# PCB_Steering_Wheel_REDO.net
KiCad netlist of a schematic drawn in Altium Designer
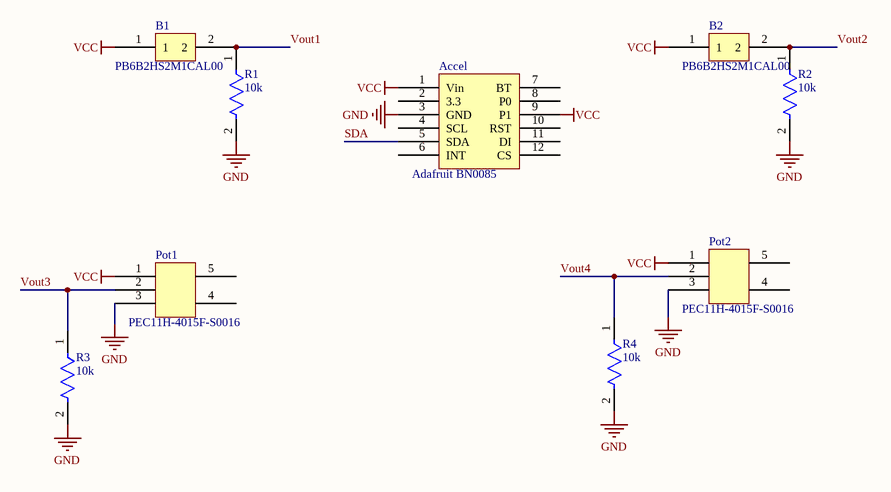
[diagram p0: PCB_Steering_Wheel_REDO.SchDoc]

(export (version "E")
  (design (tool "Eeschema 10.0.6"))
  (components
    (comp (ref "Accel")
      (value "Adafruit BN0085")
      (footprint "Adafruit BN0085-Footprint-1")
      (description "9DoF Accel/Gyro")
      (libsource (lib "Bradford Bawden") (part "New symbol 1"))
    )
    (comp (ref "B1")
      (value "PB6B2HS2M1CAL00")
      (footprint "PB6B2HS2M1CAL00-Footprint-1")
      (description "Standard PB6 Black Panel Mount Front Pushbutton Switch 125mA AC 200mA DC 125V -30C~85C")
      (libsource (lib "Bradford Bawden") (part "PB6B2HS2M1CAL00-Symbol-1"))
    )
    (comp (ref "B2")
      (value "PB6B2HS2M1CAL00")
      (footprint "PB6B2HS2M1CAL00-Footprint-1")
      (description "Standard PB6 Black Panel Mount Front Pushbutton Switch 125mA AC 200mA DC 125V -30C~85C")
      (libsource (lib "Bradford Bawden") (part "PB6B2HS2M1CAL00-Symbol-1"))
    )
    (comp (ref "Pot1")
      (value "PEC11H-4015F-S0016")
      (footprint "PEC11H-4015F-S0016-Footprint-1")
      (description "INCREMENTAL ENCODER, 2CH, 60 RPM, 16 PPR; Encoder Technology: Mechanical; Type: Incremental;")
      (libsource (lib "Bradford Bawden") (part "PEC11H-4015F-S0016-Symbol-1"))
    )
    (comp (ref "Pot2")
      (value "PEC11H-4015F-S0016")
      (footprint "PEC11H-4015F-S0016-Footprint-1")
      (description "INCREMENTAL ENCODER, 2CH, 60 RPM, 16 PPR; Encoder Technology: Mechanical; Type: Incremental;")
      (libsource (lib "Bradford Bawden") (part "PEC11H-4015F-S0016-Symbol-1"))
    )
    (comp (ref "R1")
      (value "10k")
      (footprint "FP-H45K0BAA-MFG")
      (description "RES 5.00K OHM 1/2W 0.1% AXIAL")
      (fields (field (name "TOLERANCE") "0.1%"))
      (libsource (lib "Altium Content Vault") (part "1029c3af85768c4190bb7ad29bc67b5"))
    )
    (comp (ref "R2")
      (value "10k")
      (footprint "FP-H45K0BAA-MFG")
      (description "RES 5.00K OHM 1/2W 0.1% AXIAL")
      (fields (field (name "TOLERANCE") "0.1%"))
      (libsource (lib "Altium Content Vault") (part "1029c3af85768c4190bb7ad29bc67b5"))
    )
    (comp (ref "R3")
      (value "10k")
      (footprint "FP-H45K0BAA-MFG")
      (description "RES 5.00K OHM 1/2W 0.1% AXIAL")
      (fields (field (name "TOLERANCE") "0.1%"))
      (libsource (lib "Altium Content Vault") (part "1029c3af85768c4190bb7ad29bc67b5"))
    )
    (comp (ref "R4")
      (value "10k")
      (footprint "FP-H45K0BAA-MFG")
      (description "RES 5.00K OHM 1/2W 0.1% AXIAL")
      (fields (field (name "TOLERANCE") "0.1%"))
      (libsource (lib "Altium Content Vault") (part "1029c3af85768c4190bb7ad29bc67b5"))
    )
  )
  (nets
    (net (code "1") (name "/SDA") (class "Default")
      (node (ref "Accel") (pin "5") (pinfunction "SDA_5") (pintype "passive"))
    )
    (net (code "2") (name "/Vout1") (class "Default")
      (node (ref "B1") (pin "2") (pinfunction "2_2") (pintype "passive"))
      (node (ref "R1") (pin "1") (pinfunction "1_1") (pintype "passive"))
    )
    (net (code "3") (name "/Vout2") (class "Default")
      (node (ref "B2") (pin "2") (pinfunction "2_2") (pintype "passive"))
      (node (ref "R2") (pin "1") (pinfunction "1_1") (pintype "passive"))
    )
    (net (code "4") (name "/Vout3") (class "Default")
      (node (ref "Pot1") (pin "2") (pintype "passive"))
      (node (ref "R3") (pin "1") (pinfunction "1_1") (pintype "passive"))
    )
    (net (code "5") (name "/Vout4") (class "Default")
      (node (ref "Pot2") (pin "2") (pintype "passive"))
      (node (ref "R4") (pin "1") (pinfunction "1_1") (pintype "passive"))
    )
    (net (code "6") (name "GND") (class "Default")
      (node (ref "Accel") (pin "3") (pinfunction "GND_3") (pintype "passive"))
      (node (ref "Pot1") (pin "3") (pintype "passive"))
      (node (ref "Pot2") (pin "3") (pintype "passive"))
      (node (ref "R1") (pin "2") (pinfunction "2_2") (pintype "passive"))
      (node (ref "R2") (pin "2") (pinfunction "2_2") (pintype "passive"))
      (node (ref "R3") (pin "2") (pinfunction "2_2") (pintype "passive"))
      (node (ref "R4") (pin "2") (pinfunction "2_2") (pintype "passive"))
    )
    (net (code "7") (name "VCC") (class "Default")
      (node (ref "Accel") (pin "1") (pinfunction "Vin_1") (pintype "passive"))
      (node (ref "Accel") (pin "9") (pinfunction "P1_9") (pintype "passive"))
      (node (ref "B1") (pin "1") (pinfunction "1_1") (pintype "passive"))
      (node (ref "B2") (pin "1") (pinfunction "1_1") (pintype "passive"))
      (node (ref "Pot1") (pin "1") (pintype "passive"))
      (node (ref "Pot2") (pin "1") (pintype "passive"))
    )
    (net (code "8") (name "unconnected-(Accel-3.3-Pad2)") (class "Default")
      (node (ref "Accel") (pin "2") (pinfunction "3.3_2") (pintype "passive"))
    )
    (net (code "9") (name "unconnected-(Accel-BT-Pad7)") (class "Default")
      (node (ref "Accel") (pin "7") (pinfunction "BT_7") (pintype "passive"))
    )
    (net (code "10") (name "unconnected-(Accel-CS-Pad12)") (class "Default")
      (node (ref "Accel") (pin "12") (pinfunction "CS_12") (pintype "passive"))
    )
    (net (code "11") (name "unconnected-(Accel-DI-Pad11)") (class "Default")
      (node (ref "Accel") (pin "11") (pinfunction "DI_11") (pintype "passive"))
    )
    (net (code "12") (name "unconnected-(Accel-INT-Pad6)") (class "Default")
      (node (ref "Accel") (pin "6") (pinfunction "INT_6") (pintype "passive"))
    )
    (net (code "13") (name "unconnected-(Accel-P0-Pad8)") (class "Default")
      (node (ref "Accel") (pin "8") (pinfunction "P0_8") (pintype "passive"))
    )
    (net (code "14") (name "unconnected-(Accel-RST-Pad10)") (class "Default")
      (node (ref "Accel") (pin "10") (pinfunction "RST_10") (pintype "passive"))
    )
    (net (code "15") (name "unconnected-(Accel-SCL-Pad4)") (class "Default")
      (node (ref "Accel") (pin "4") (pinfunction "SCL_4") (pintype "passive"))
    )
    (net (code "16") (name "unconnected-(Pot1-Pad4)") (class "Default")
      (node (ref "Pot1") (pin "4") (pintype "passive"))
    )
    (net (code "17") (name "unconnected-(Pot1-Pad5)") (class "Default")
      (node (ref "Pot1") (pin "5") (pintype "passive"))
    )
    (net (code "18") (name "unconnected-(Pot2-Pad4)") (class "Default")
      (node (ref "Pot2") (pin "4") (pintype "passive"))
    )
    (net (code "19") (name "unconnected-(Pot2-Pad5)") (class "Default")
      (node (ref "Pot2") (pin "5") (pintype "passive"))
    )
  )
)
